# Snippet_STMF103C8T6.net
KiCad netlist of a schematic drawn in Altium Designer
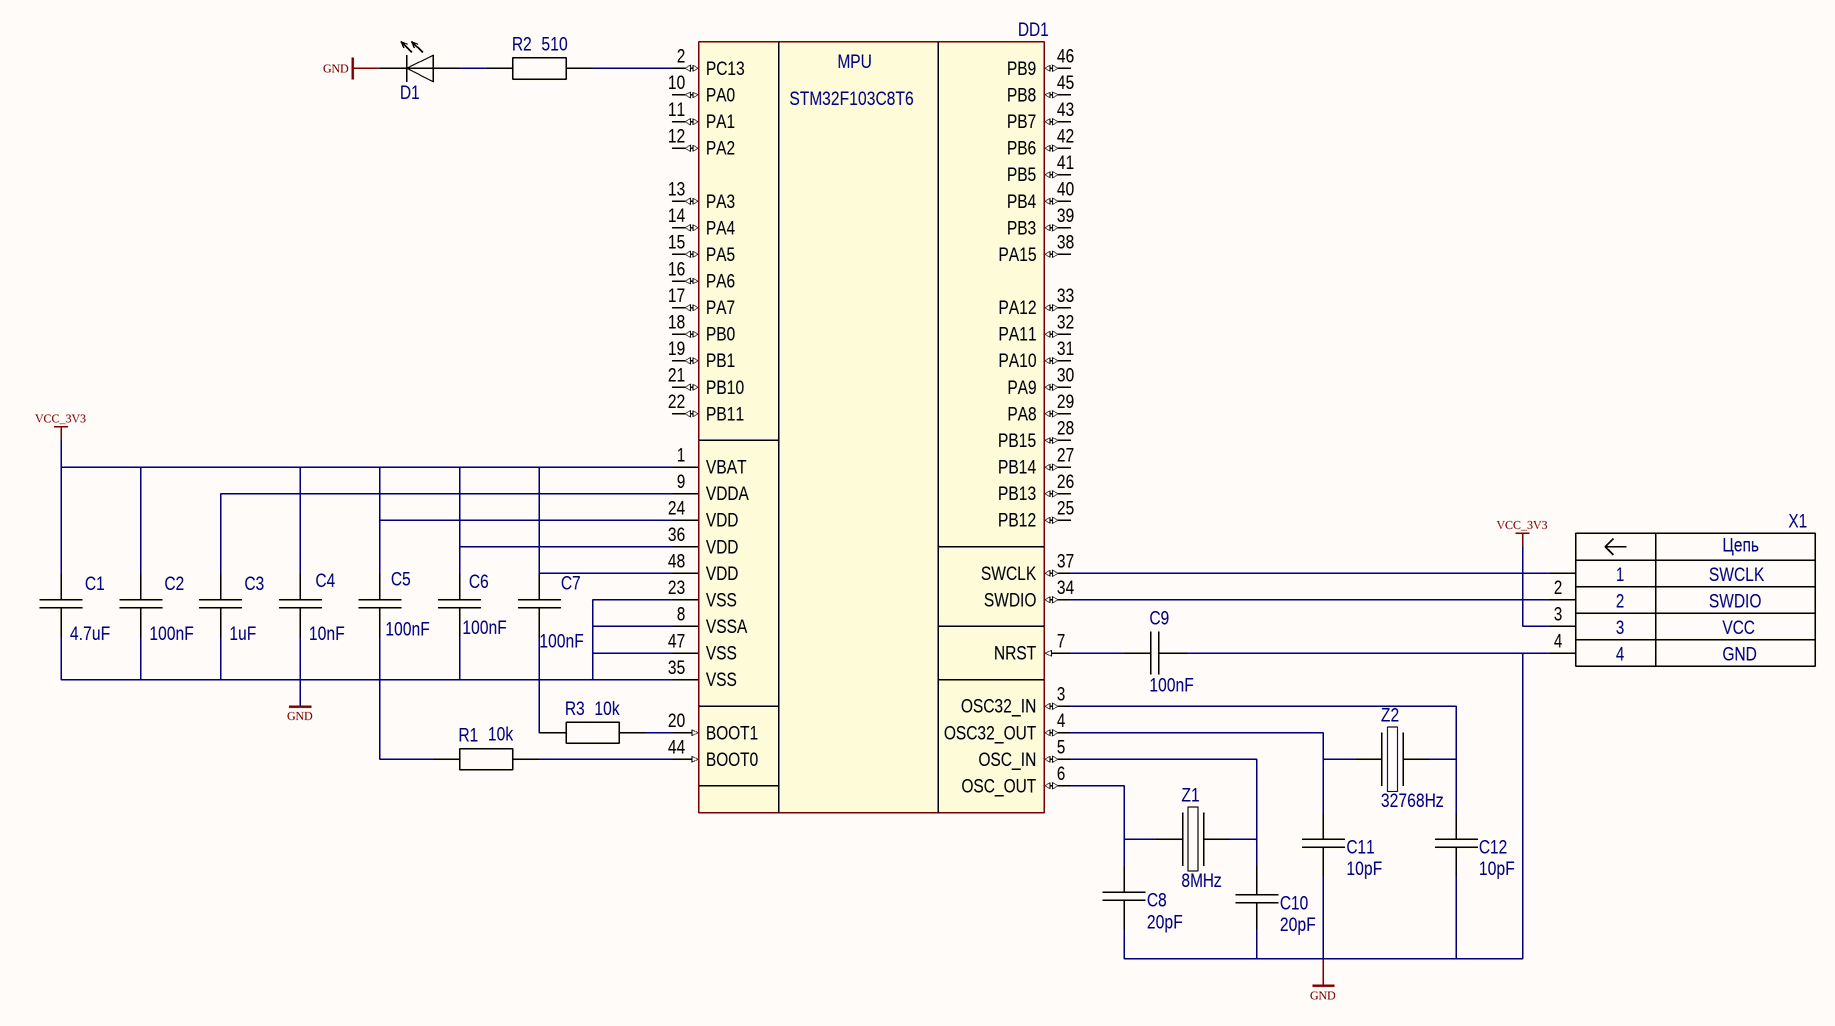
[diagram p0: Snippet_STMF103C8T6.SchDoc]

(export (version "E")
  (design (tool "Eeschema 10.0.6"))
  (components
    (comp (ref "C1")
      (value "4.7uF")
      (footprint "Capacitor_0805")
      (libsource (lib "Библиотека элементов") (part "Capacitor_0805"))
    )
    (comp (ref "C2")
      (value "100nF")
      (footprint "Capacitor_0805")
      (libsource (lib "Библиотека элементов") (part "Capacitor_0805"))
    )
    (comp (ref "C3")
      (value "1uF")
      (footprint "Capacitor_0805")
      (libsource (lib "Библиотека элементов") (part "Capacitor_0805"))
    )
    (comp (ref "C4")
      (value "10nF")
      (footprint "Capacitor_0805")
      (libsource (lib "Библиотека элементов") (part "Capacitor_0805"))
    )
    (comp (ref "C5")
      (value "100nF")
      (footprint "Capacitor_0805")
      (libsource (lib "Библиотека элементов") (part "Capacitor_0805"))
    )
    (comp (ref "C6")
      (value "100nF")
      (footprint "Capacitor_0805")
      (libsource (lib "Библиотека элементов") (part "Capacitor_0805"))
    )
    (comp (ref "C7")
      (value "100nF")
      (footprint "Capacitor_0805")
      (libsource (lib "Библиотека элементов") (part "Capacitor_0805"))
    )
    (comp (ref "C8")
      (value "20pF")
      (footprint "Capacitor_0805")
      (libsource (lib "Библиотека элементов") (part "Capacitor_0805"))
    )
    (comp (ref "C9")
      (value "100nF")
      (footprint "Capacitor_0805")
      (libsource (lib "Библиотека элементов") (part "Capacitor_0805"))
    )
    (comp (ref "C10")
      (value "20pF")
      (footprint "Capacitor_0805")
      (libsource (lib "Библиотека элементов") (part "Capacitor_0805"))
    )
    (comp (ref "C11")
      (value "10pF")
      (footprint "Capacitor_0805")
      (libsource (lib "Библиотека элементов") (part "Capacitor_0805"))
    )
    (comp (ref "C12")
      (value "10pF")
      (footprint "Capacitor_0805")
      (libsource (lib "Библиотека элементов") (part "Capacitor_0805"))
    )
    (comp (ref "D1")
      (value "LED_0805_G")
      (footprint "LED_0805_G")
      (description "KP-2012MGC")
      (libsource (lib "Библиотека элементов") (part "LED_0805_G"))
    )
    (comp (ref "DD1")
      (value "STM32F103C8T6")
      (footprint "LQFP48")
      (libsource (lib "Библиотека элементов") (part "STM32F103C8T6"))
    )
    (comp (ref "R1")
      (value "10k")
      (footprint "RESISTOR_SMD0805")
      (libsource (lib "Библиотека элементов") (part "Resistor_0805"))
    )
    (comp (ref "R2")
      (value "510")
      (footprint "RESISTOR_SMD0805")
      (libsource (lib "Библиотека элементов") (part "Resistor_0805"))
    )
    (comp (ref "R3")
      (value "10k")
      (footprint "RESISTOR_SMD0805")
      (libsource (lib "Библиотека элементов") (part "Resistor_0805"))
    )
    (comp (ref "X1")
      (value "Connector_PLS-4")
      (footprint "CONNECTOR_PLS-4")
      (libsource (lib "Библиотека элементов") (part "Connector_PLS-4"))
    )
    (comp (ref "Z1")
      (value "8MHz")
      (footprint "Quartz_KX-9")
      (libsource (lib "Библиотека элементов") (part "Quartz_KX-9A"))
    )
    (comp (ref "Z2")
      (value "32768Hz")
      (footprint "Quartz_32768kHz")
      (libsource (lib "Библиотека элементов") (part "Quartz_32678Hz"))
    )
  )
  (nets
    (net (code "1") (name "GND") (class "Default")
      (node (ref "C1") (pin "1") (pinfunction "1_1") (pintype "passive"))
      (node (ref "C10") (pin "2") (pinfunction "2_2") (pintype "passive"))
      (node (ref "C11") (pin "1") (pinfunction "1_1") (pintype "passive"))
      (node (ref "C12") (pin "1") (pinfunction "1_1") (pintype "passive"))
      (node (ref "C2") (pin "1") (pinfunction "1_1") (pintype "passive"))
      (node (ref "C3") (pin "1") (pinfunction "1_1") (pintype "passive"))
      (node (ref "C4") (pin "1") (pinfunction "1_1") (pintype "passive"))
      (node (ref "C5") (pin "1") (pinfunction "1_1") (pintype "passive"))
      (node (ref "C6") (pin "1") (pinfunction "1_1") (pintype "passive"))
      (node (ref "C7") (pin "1") (pinfunction "1_1") (pintype "passive"))
      (node (ref "C8") (pin "1") (pinfunction "1_1") (pintype "passive"))
      (node (ref "C9") (pin "1") (pinfunction "1_1") (pintype "passive"))
      (node (ref "D1") (pin "2") (pinfunction "2_2") (pintype "passive"))
      (node (ref "DD1") (pin "23") (pinfunction "VSS_23") (pintype "power_in"))
      (node (ref "DD1") (pin "35") (pinfunction "VSS_35") (pintype "power_in"))
      (node (ref "DD1") (pin "47") (pinfunction "VSS_47") (pintype "power_in"))
      (node (ref "DD1") (pin "8") (pinfunction "VSSA_8") (pintype "power_in"))
      (node (ref "R1") (pin "2") (pinfunction "2_2") (pintype "passive"))
      (node (ref "R3") (pin "2") (pinfunction "2_2") (pintype "passive"))
      (node (ref "X1") (pin "4") (pinfunction "4_4") (pintype "passive"))
    )
    (net (code "2") (name "Net-(D1-Pad1)") (class "Default")
      (node (ref "D1") (pin "1") (pinfunction "1_1") (pintype "passive"))
      (node (ref "R2") (pin "2") (pinfunction "2_2") (pintype "passive"))
    )
    (net (code "3") (name "Net-(DD1-BOOT0)") (class "Default")
      (node (ref "DD1") (pin "44") (pinfunction "BOOT0_44") (pintype "input"))
      (node (ref "R1") (pin "1") (pinfunction "1_1") (pintype "passive"))
    )
    (net (code "4") (name "Net-(DD1-BOOT1)") (class "Default")
      (node (ref "DD1") (pin "20") (pinfunction "BOOT1_20") (pintype "input"))
      (node (ref "R3") (pin "1") (pinfunction "1_1") (pintype "passive"))
    )
    (net (code "5") (name "Net-(DD1-NRST)") (class "Default")
      (node (ref "C9") (pin "2") (pinfunction "2_2") (pintype "passive"))
      (node (ref "DD1") (pin "7") (pinfunction "NRST_7") (pintype "input"))
    )
    (net (code "6") (name "Net-(DD1-OSC32_IN)") (class "Default")
      (node (ref "C12") (pin "2") (pinfunction "2_2") (pintype "passive"))
      (node (ref "DD1") (pin "3") (pinfunction "OSC32_IN_3") (pintype "bidirectional"))
      (node (ref "Z2") (pin "1") (pinfunction "1_1") (pintype "passive"))
    )
    (net (code "7") (name "Net-(DD1-OSC32_OUT)") (class "Default")
      (node (ref "C11") (pin "2") (pinfunction "2_2") (pintype "passive"))
      (node (ref "DD1") (pin "4") (pinfunction "OSC32_OUT_4") (pintype "bidirectional"))
      (node (ref "Z2") (pin "2") (pinfunction "2_2") (pintype "passive"))
    )
    (net (code "8") (name "Net-(DD1-OSC_IN)") (class "Default")
      (node (ref "C10") (pin "1") (pinfunction "1_1") (pintype "passive"))
      (node (ref "DD1") (pin "5") (pinfunction "OSC_IN_5") (pintype "bidirectional"))
      (node (ref "Z1") (pin "3") (pinfunction "3_3") (pintype "passive"))
    )
    (net (code "9") (name "Net-(DD1-OSC_OUT)") (class "Default")
      (node (ref "C8") (pin "2") (pinfunction "2_2") (pintype "passive"))
      (node (ref "DD1") (pin "6") (pinfunction "OSC_OUT_6") (pintype "bidirectional"))
      (node (ref "Z1") (pin "1") (pinfunction "1_1") (pintype "passive"))
    )
    (net (code "10") (name "Net-(DD1-PC13)") (class "Default")
      (node (ref "DD1") (pin "2") (pinfunction "PC13_2") (pintype "bidirectional"))
      (node (ref "R2") (pin "1") (pinfunction "1_1") (pintype "passive"))
    )
    (net (code "11") (name "Net-(DD1-SWCLK)") (class "Default")
      (node (ref "DD1") (pin "37") (pinfunction "SWCLK_37") (pintype "bidirectional"))
      (node (ref "X1") (pin "1") (pinfunction "1_1") (pintype "passive"))
    )
    (net (code "12") (name "Net-(DD1-SWDIO)") (class "Default")
      (node (ref "DD1") (pin "34") (pinfunction "SWDIO_34") (pintype "bidirectional"))
      (node (ref "X1") (pin "2") (pinfunction "2_2") (pintype "passive"))
    )
    (net (code "13") (name "VCC_3V3") (class "Default")
      (node (ref "C1") (pin "2") (pinfunction "2_2") (pintype "passive"))
      (node (ref "C2") (pin "2") (pinfunction "2_2") (pintype "passive"))
      (node (ref "C3") (pin "2") (pinfunction "2_2") (pintype "passive"))
      (node (ref "C4") (pin "2") (pinfunction "2_2") (pintype "passive"))
      (node (ref "C5") (pin "2") (pinfunction "2_2") (pintype "passive"))
      (node (ref "C6") (pin "2") (pinfunction "2_2") (pintype "passive"))
      (node (ref "C7") (pin "2") (pinfunction "2_2") (pintype "passive"))
      (node (ref "DD1") (pin "1") (pinfunction "VBAT_1") (pintype "power_in"))
      (node (ref "DD1") (pin "24") (pinfunction "VDD_24") (pintype "power_in"))
      (node (ref "DD1") (pin "36") (pinfunction "VDD_36") (pintype "power_in"))
      (node (ref "DD1") (pin "48") (pinfunction "VDD_48") (pintype "power_in"))
      (node (ref "DD1") (pin "9") (pinfunction "VDDA_9") (pintype "power_in"))
      (node (ref "X1") (pin "3") (pinfunction "3_3") (pintype "passive"))
    )
    (net (code "14") (name "unconnected-(DD1-PA0-Pad10)") (class "Default")
      (node (ref "DD1") (pin "10") (pinfunction "PA0_10") (pintype "bidirectional"))
    )
    (net (code "15") (name "unconnected-(DD1-PA1-Pad11)") (class "Default")
      (node (ref "DD1") (pin "11") (pinfunction "PA1_11") (pintype "bidirectional"))
    )
    (net (code "16") (name "unconnected-(DD1-PA2-Pad12)") (class "Default")
      (node (ref "DD1") (pin "12") (pinfunction "PA2_12") (pintype "bidirectional"))
    )
    (net (code "17") (name "unconnected-(DD1-PA3-Pad13)") (class "Default")
      (node (ref "DD1") (pin "13") (pinfunction "PA3_13") (pintype "bidirectional"))
    )
    (net (code "18") (name "unconnected-(DD1-PA4-Pad14)") (class "Default")
      (node (ref "DD1") (pin "14") (pinfunction "PA4_14") (pintype "bidirectional"))
    )
    (net (code "19") (name "unconnected-(DD1-PA5-Pad15)") (class "Default")
      (node (ref "DD1") (pin "15") (pinfunction "PA5_15") (pintype "bidirectional"))
    )
    (net (code "20") (name "unconnected-(DD1-PA6-Pad16)") (class "Default")
      (node (ref "DD1") (pin "16") (pinfunction "PA6_16") (pintype "bidirectional"))
    )
    (net (code "21") (name "unconnected-(DD1-PA7-Pad17)") (class "Default")
      (node (ref "DD1") (pin "17") (pinfunction "PA7_17") (pintype "bidirectional"))
    )
    (net (code "22") (name "unconnected-(DD1-PA8-Pad29)") (class "Default")
      (node (ref "DD1") (pin "29") (pinfunction "PA8_29") (pintype "bidirectional"))
    )
    (net (code "23") (name "unconnected-(DD1-PA9-Pad30)") (class "Default")
      (node (ref "DD1") (pin "30") (pinfunction "PA9_30") (pintype "bidirectional"))
    )
    (net (code "24") (name "unconnected-(DD1-PA10-Pad31)") (class "Default")
      (node (ref "DD1") (pin "31") (pinfunction "PA10_31") (pintype "bidirectional"))
    )
    (net (code "25") (name "unconnected-(DD1-PA11-Pad32)") (class "Default")
      (node (ref "DD1") (pin "32") (pinfunction "PA11_32") (pintype "bidirectional"))
    )
    (net (code "26") (name "unconnected-(DD1-PA12-Pad33)") (class "Default")
      (node (ref "DD1") (pin "33") (pinfunction "PA12_33") (pintype "bidirectional"))
    )
    (net (code "27") (name "unconnected-(DD1-PA15-Pad38)") (class "Default")
      (node (ref "DD1") (pin "38") (pinfunction "PA15_38") (pintype "bidirectional"))
    )
    (net (code "28") (name "unconnected-(DD1-PB0-Pad18)") (class "Default")
      (node (ref "DD1") (pin "18") (pinfunction "PB0_18") (pintype "bidirectional"))
    )
    (net (code "29") (name "unconnected-(DD1-PB1-Pad19)") (class "Default")
      (node (ref "DD1") (pin "19") (pinfunction "PB1_19") (pintype "bidirectional"))
    )
    (net (code "30") (name "unconnected-(DD1-PB3-Pad39)") (class "Default")
      (node (ref "DD1") (pin "39") (pinfunction "PB3_39") (pintype "bidirectional"))
    )
    (net (code "31") (name "unconnected-(DD1-PB4-Pad40)") (class "Default")
      (node (ref "DD1") (pin "40") (pinfunction "PB4_40") (pintype "bidirectional"))
    )
    (net (code "32") (name "unconnected-(DD1-PB5-Pad41)") (class "Default")
      (node (ref "DD1") (pin "41") (pinfunction "PB5_41") (pintype "bidirectional"))
    )
    (net (code "33") (name "unconnected-(DD1-PB6-Pad42)") (class "Default")
      (node (ref "DD1") (pin "42") (pinfunction "PB6_42") (pintype "bidirectional"))
    )
    (net (code "34") (name "unconnected-(DD1-PB7-Pad43)") (class "Default")
      (node (ref "DD1") (pin "43") (pinfunction "PB7_43") (pintype "bidirectional"))
    )
    (net (code "35") (name "unconnected-(DD1-PB8-Pad45)") (class "Default")
      (node (ref "DD1") (pin "45") (pinfunction "PB8_45") (pintype "bidirectional"))
    )
    (net (code "36") (name "unconnected-(DD1-PB9-Pad46)") (class "Default")
      (node (ref "DD1") (pin "46") (pinfunction "PB9_46") (pintype "bidirectional"))
    )
    (net (code "37") (name "unconnected-(DD1-PB10-Pad21)") (class "Default")
      (node (ref "DD1") (pin "21") (pinfunction "PB10_21") (pintype "bidirectional"))
    )
    (net (code "38") (name "unconnected-(DD1-PB11-Pad22)") (class "Default")
      (node (ref "DD1") (pin "22") (pinfunction "PB11_22") (pintype "bidirectional"))
    )
    (net (code "39") (name "unconnected-(DD1-PB12-Pad25)") (class "Default")
      (node (ref "DD1") (pin "25") (pinfunction "PB12_25") (pintype "bidirectional"))
    )
    (net (code "40") (name "unconnected-(DD1-PB13-Pad26)") (class "Default")
      (node (ref "DD1") (pin "26") (pinfunction "PB13_26") (pintype "bidirectional"))
    )
    (net (code "41") (name "unconnected-(DD1-PB14-Pad27)") (class "Default")
      (node (ref "DD1") (pin "27") (pinfunction "PB14_27") (pintype "bidirectional"))
    )
    (net (code "42") (name "unconnected-(DD1-PB15-Pad28)") (class "Default")
      (node (ref "DD1") (pin "28") (pinfunction "PB15_28") (pintype "bidirectional"))
    )
  )
)
